# Cubesat_Linear.net
KiCad netlist of a schematic drawn in EAGLE
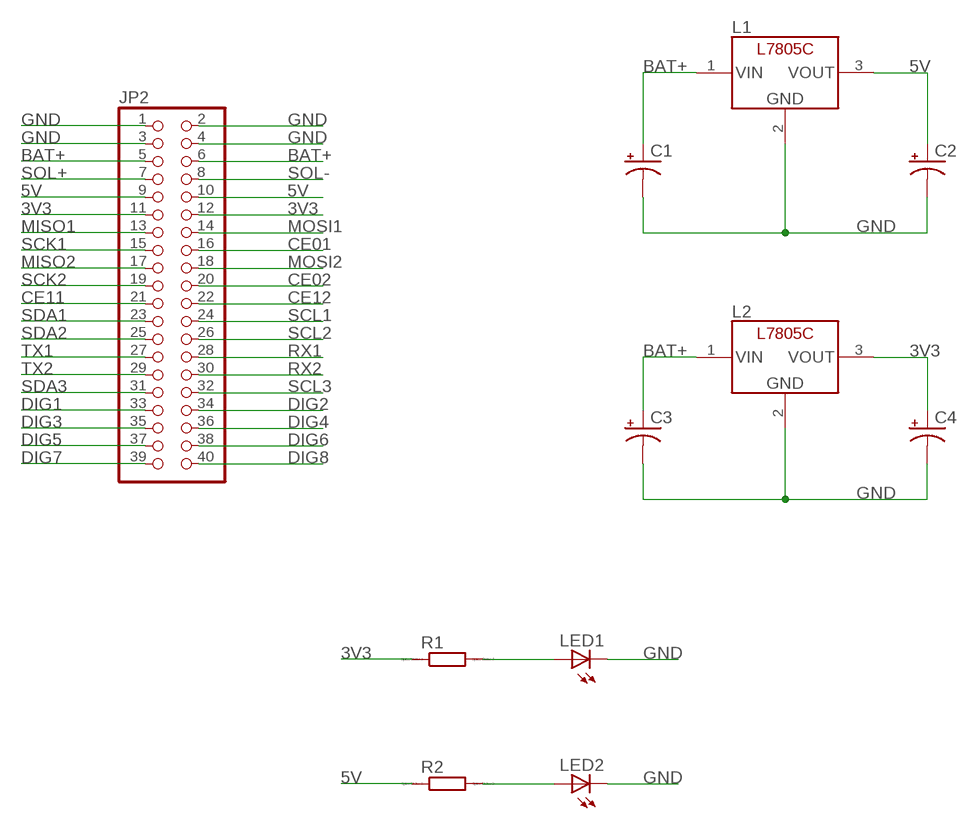
[diagram p0: schematic, sheet 1]

(export (version "E")
  (design (tool "Eeschema 10.0.6"))
  (components
    (comp (ref "C1")
      (value "CAP_POLC")
      (footprint "eagle-import:PANASONIC_C")
      (libsource (lib "eagle-import") (part "CAP_POLC"))
    )
    (comp (ref "C2")
      (value "CAP_POLC")
      (footprint "eagle-import:PANASONIC_C")
      (libsource (lib "eagle-import") (part "CAP_POLC"))
    )
    (comp (ref "C3")
      (value "CAP_POLC")
      (footprint "eagle-import:PANASONIC_C")
      (libsource (lib "eagle-import") (part "CAP_POLC"))
    )
    (comp (ref "C4")
      (value "CAP_POLC")
      (footprint "eagle-import:PANASONIC_C")
      (libsource (lib "eagle-import") (part "CAP_POLC"))
    )
    (comp (ref "JP2")
      (value "PINHD-2X20")
      (footprint "eagle-import:2X20")
      (libsource (lib "eagle-import") (part "PINHD-2X20"))
    )
    (comp (ref "L1")
      (value "L7805C")
      (footprint "eagle-import:TO-220")
      (libsource (lib "eagle-import") (part "L7805C"))
    )
    (comp (ref "L2")
      (value "L7805C")
      (footprint "eagle-import:TO-220")
      (libsource (lib "eagle-import") (part "L7805C"))
    )
    (comp (ref "LED1")
      (value "LEDCHIPLED_1206")
      (footprint "eagle-import:CHIPLED_1206")
      (libsource (lib "eagle-import") (part "LEDCHIPLED_1206"))
    )
    (comp (ref "LED2")
      (value "LEDCHIPLED_1206")
      (footprint "eagle-import:CHIPLED_1206")
      (libsource (lib "eagle-import") (part "LEDCHIPLED_1206"))
    )
    (comp (ref "R1")
      (value "RR1206")
      (footprint "eagle-import:R1206")
      (libsource (lib "eagle-import") (part "RR1206"))
    )
    (comp (ref "R2")
      (value "RR1206")
      (footprint "eagle-import:R1206")
      (libsource (lib "eagle-import") (part "RR1206"))
    )
  )
  (nets
    (net (code "1") (name "/3V3") (class "Default")
      (node (ref "C4") (pin "+") (pinfunction "+_+") (pintype "passive"))
      (node (ref "JP2") (pin "11") (pinfunction "11_11") (pintype "passive"))
      (node (ref "JP2") (pin "12") (pinfunction "12_12") (pintype "passive"))
      (node (ref "L2") (pin "3") (pinfunction "VOUT_3") (pintype "bidirectional"))
      (node (ref "R1") (pin "1") (pinfunction "1_1") (pintype "passive"))
    )
    (net (code "2") (name "/5V") (class "Default")
      (node (ref "C2") (pin "+") (pinfunction "+_+") (pintype "passive"))
      (node (ref "JP2") (pin "10") (pinfunction "10_10") (pintype "passive"))
      (node (ref "JP2") (pin "9") (pinfunction "9_9") (pintype "passive"))
      (node (ref "L1") (pin "3") (pinfunction "VOUT_3") (pintype "bidirectional"))
      (node (ref "R2") (pin "1") (pinfunction "1_1") (pintype "passive"))
    )
    (net (code "3") (name "/BAT+") (class "Default")
      (node (ref "C1") (pin "+") (pinfunction "+_+") (pintype "passive"))
      (node (ref "C3") (pin "+") (pinfunction "+_+") (pintype "passive"))
      (node (ref "JP2") (pin "5") (pinfunction "5_5") (pintype "passive"))
      (node (ref "JP2") (pin "6") (pinfunction "6_6") (pintype "passive"))
      (node (ref "L1") (pin "1") (pinfunction "VIN_1") (pintype "bidirectional"))
      (node (ref "L2") (pin "1") (pinfunction "VIN_1") (pintype "bidirectional"))
    )
    (net (code "4") (name "/CE01") (class "Default")
      (node (ref "JP2") (pin "16") (pinfunction "16_16") (pintype "passive"))
    )
    (net (code "5") (name "/CE02") (class "Default")
      (node (ref "JP2") (pin "20") (pinfunction "20_20") (pintype "passive"))
    )
    (net (code "6") (name "/CE11") (class "Default")
      (node (ref "JP2") (pin "21") (pinfunction "21_21") (pintype "passive"))
    )
    (net (code "7") (name "/CE12") (class "Default")
      (node (ref "JP2") (pin "22") (pinfunction "22_22") (pintype "passive"))
    )
    (net (code "8") (name "/DIG1") (class "Default")
      (node (ref "JP2") (pin "33") (pinfunction "33_33") (pintype "passive"))
    )
    (net (code "9") (name "/DIG2") (class "Default")
      (node (ref "JP2") (pin "34") (pinfunction "34_34") (pintype "passive"))
    )
    (net (code "10") (name "/DIG3") (class "Default")
      (node (ref "JP2") (pin "35") (pinfunction "35_35") (pintype "passive"))
    )
    (net (code "11") (name "/DIG4") (class "Default")
      (node (ref "JP2") (pin "36") (pinfunction "36_36") (pintype "passive"))
    )
    (net (code "12") (name "/DIG5") (class "Default")
      (node (ref "JP2") (pin "37") (pinfunction "37_37") (pintype "passive"))
    )
    (net (code "13") (name "/DIG6") (class "Default")
      (node (ref "JP2") (pin "38") (pinfunction "38_38") (pintype "passive"))
    )
    (net (code "14") (name "/DIG7") (class "Default")
      (node (ref "JP2") (pin "39") (pinfunction "39_39") (pintype "passive"))
    )
    (net (code "15") (name "/DIG8") (class "Default")
      (node (ref "JP2") (pin "40") (pinfunction "40_40") (pintype "passive"))
    )
    (net (code "16") (name "/GND") (class "Default")
      (node (ref "C1") (pin "-") (pinfunction "-_-") (pintype "passive"))
      (node (ref "C2") (pin "-") (pinfunction "-_-") (pintype "passive"))
      (node (ref "C3") (pin "-") (pinfunction "-_-") (pintype "passive"))
      (node (ref "C4") (pin "-") (pinfunction "-_-") (pintype "passive"))
      (node (ref "JP2") (pin "1") (pinfunction "1_1") (pintype "passive"))
      (node (ref "JP2") (pin "2") (pinfunction "2_2") (pintype "passive"))
      (node (ref "JP2") (pin "3") (pinfunction "3_3") (pintype "passive"))
      (node (ref "JP2") (pin "4") (pinfunction "4_4") (pintype "passive"))
      (node (ref "L1") (pin "2") (pinfunction "GND_2") (pintype "bidirectional"))
      (node (ref "L2") (pin "2") (pinfunction "GND_2") (pintype "bidirectional"))
      (node (ref "LED1") (pin "C") (pinfunction "C_C") (pintype "passive"))
      (node (ref "LED2") (pin "C") (pinfunction "C_C") (pintype "passive"))
    )
    (net (code "17") (name "/MISO1") (class "Default")
      (node (ref "JP2") (pin "13") (pinfunction "13_13") (pintype "passive"))
    )
    (net (code "18") (name "/MISO2") (class "Default")
      (node (ref "JP2") (pin "17") (pinfunction "17_17") (pintype "passive"))
    )
    (net (code "19") (name "/MOSI1") (class "Default")
      (node (ref "JP2") (pin "14") (pinfunction "14_14") (pintype "passive"))
    )
    (net (code "20") (name "/MOSI2") (class "Default")
      (node (ref "JP2") (pin "18") (pinfunction "18_18") (pintype "passive"))
    )
    (net (code "21") (name "/RX1") (class "Default")
      (node (ref "JP2") (pin "28") (pinfunction "28_28") (pintype "passive"))
    )
    (net (code "22") (name "/RX2") (class "Default")
      (node (ref "JP2") (pin "30") (pinfunction "30_30") (pintype "passive"))
    )
    (net (code "23") (name "/SCK1") (class "Default")
      (node (ref "JP2") (pin "15") (pinfunction "15_15") (pintype "passive"))
    )
    (net (code "24") (name "/SCK2") (class "Default")
      (node (ref "JP2") (pin "19") (pinfunction "19_19") (pintype "passive"))
    )
    (net (code "25") (name "/SCL1") (class "Default")
      (node (ref "JP2") (pin "24") (pinfunction "24_24") (pintype "passive"))
    )
    (net (code "26") (name "/SCL2") (class "Default")
      (node (ref "JP2") (pin "26") (pinfunction "26_26") (pintype "passive"))
    )
    (net (code "27") (name "/SCL3") (class "Default")
      (node (ref "JP2") (pin "32") (pinfunction "32_32") (pintype "passive"))
    )
    (net (code "28") (name "/SDA1") (class "Default")
      (node (ref "JP2") (pin "23") (pinfunction "23_23") (pintype "passive"))
    )
    (net (code "29") (name "/SDA2") (class "Default")
      (node (ref "JP2") (pin "25") (pinfunction "25_25") (pintype "passive"))
    )
    (net (code "30") (name "/SDA3") (class "Default")
      (node (ref "JP2") (pin "31") (pinfunction "31_31") (pintype "passive"))
    )
    (net (code "31") (name "/SOL+") (class "Default")
      (node (ref "JP2") (pin "7") (pinfunction "7_7") (pintype "passive"))
    )
    (net (code "32") (name "/SOL-") (class "Default")
      (node (ref "JP2") (pin "8") (pinfunction "8_8") (pintype "passive"))
    )
    (net (code "33") (name "/TX1") (class "Default")
      (node (ref "JP2") (pin "27") (pinfunction "27_27") (pintype "passive"))
    )
    (net (code "34") (name "/TX2") (class "Default")
      (node (ref "JP2") (pin "29") (pinfunction "29_29") (pintype "passive"))
    )
    (net (code "35") (name "Net-(LED1-PadA)") (class "Default")
      (node (ref "LED1") (pin "A") (pinfunction "A_A") (pintype "passive"))
      (node (ref "R1") (pin "2") (pinfunction "2_2") (pintype "passive"))
    )
    (net (code "36") (name "Net-(LED2-PadA)") (class "Default")
      (node (ref "LED2") (pin "A") (pinfunction "A_A") (pintype "passive"))
      (node (ref "R2") (pin "2") (pinfunction "2_2") (pintype "passive"))
    )
  )
)
